# activator.net
KiCad netlist of a schematic drawn in Altium Designer
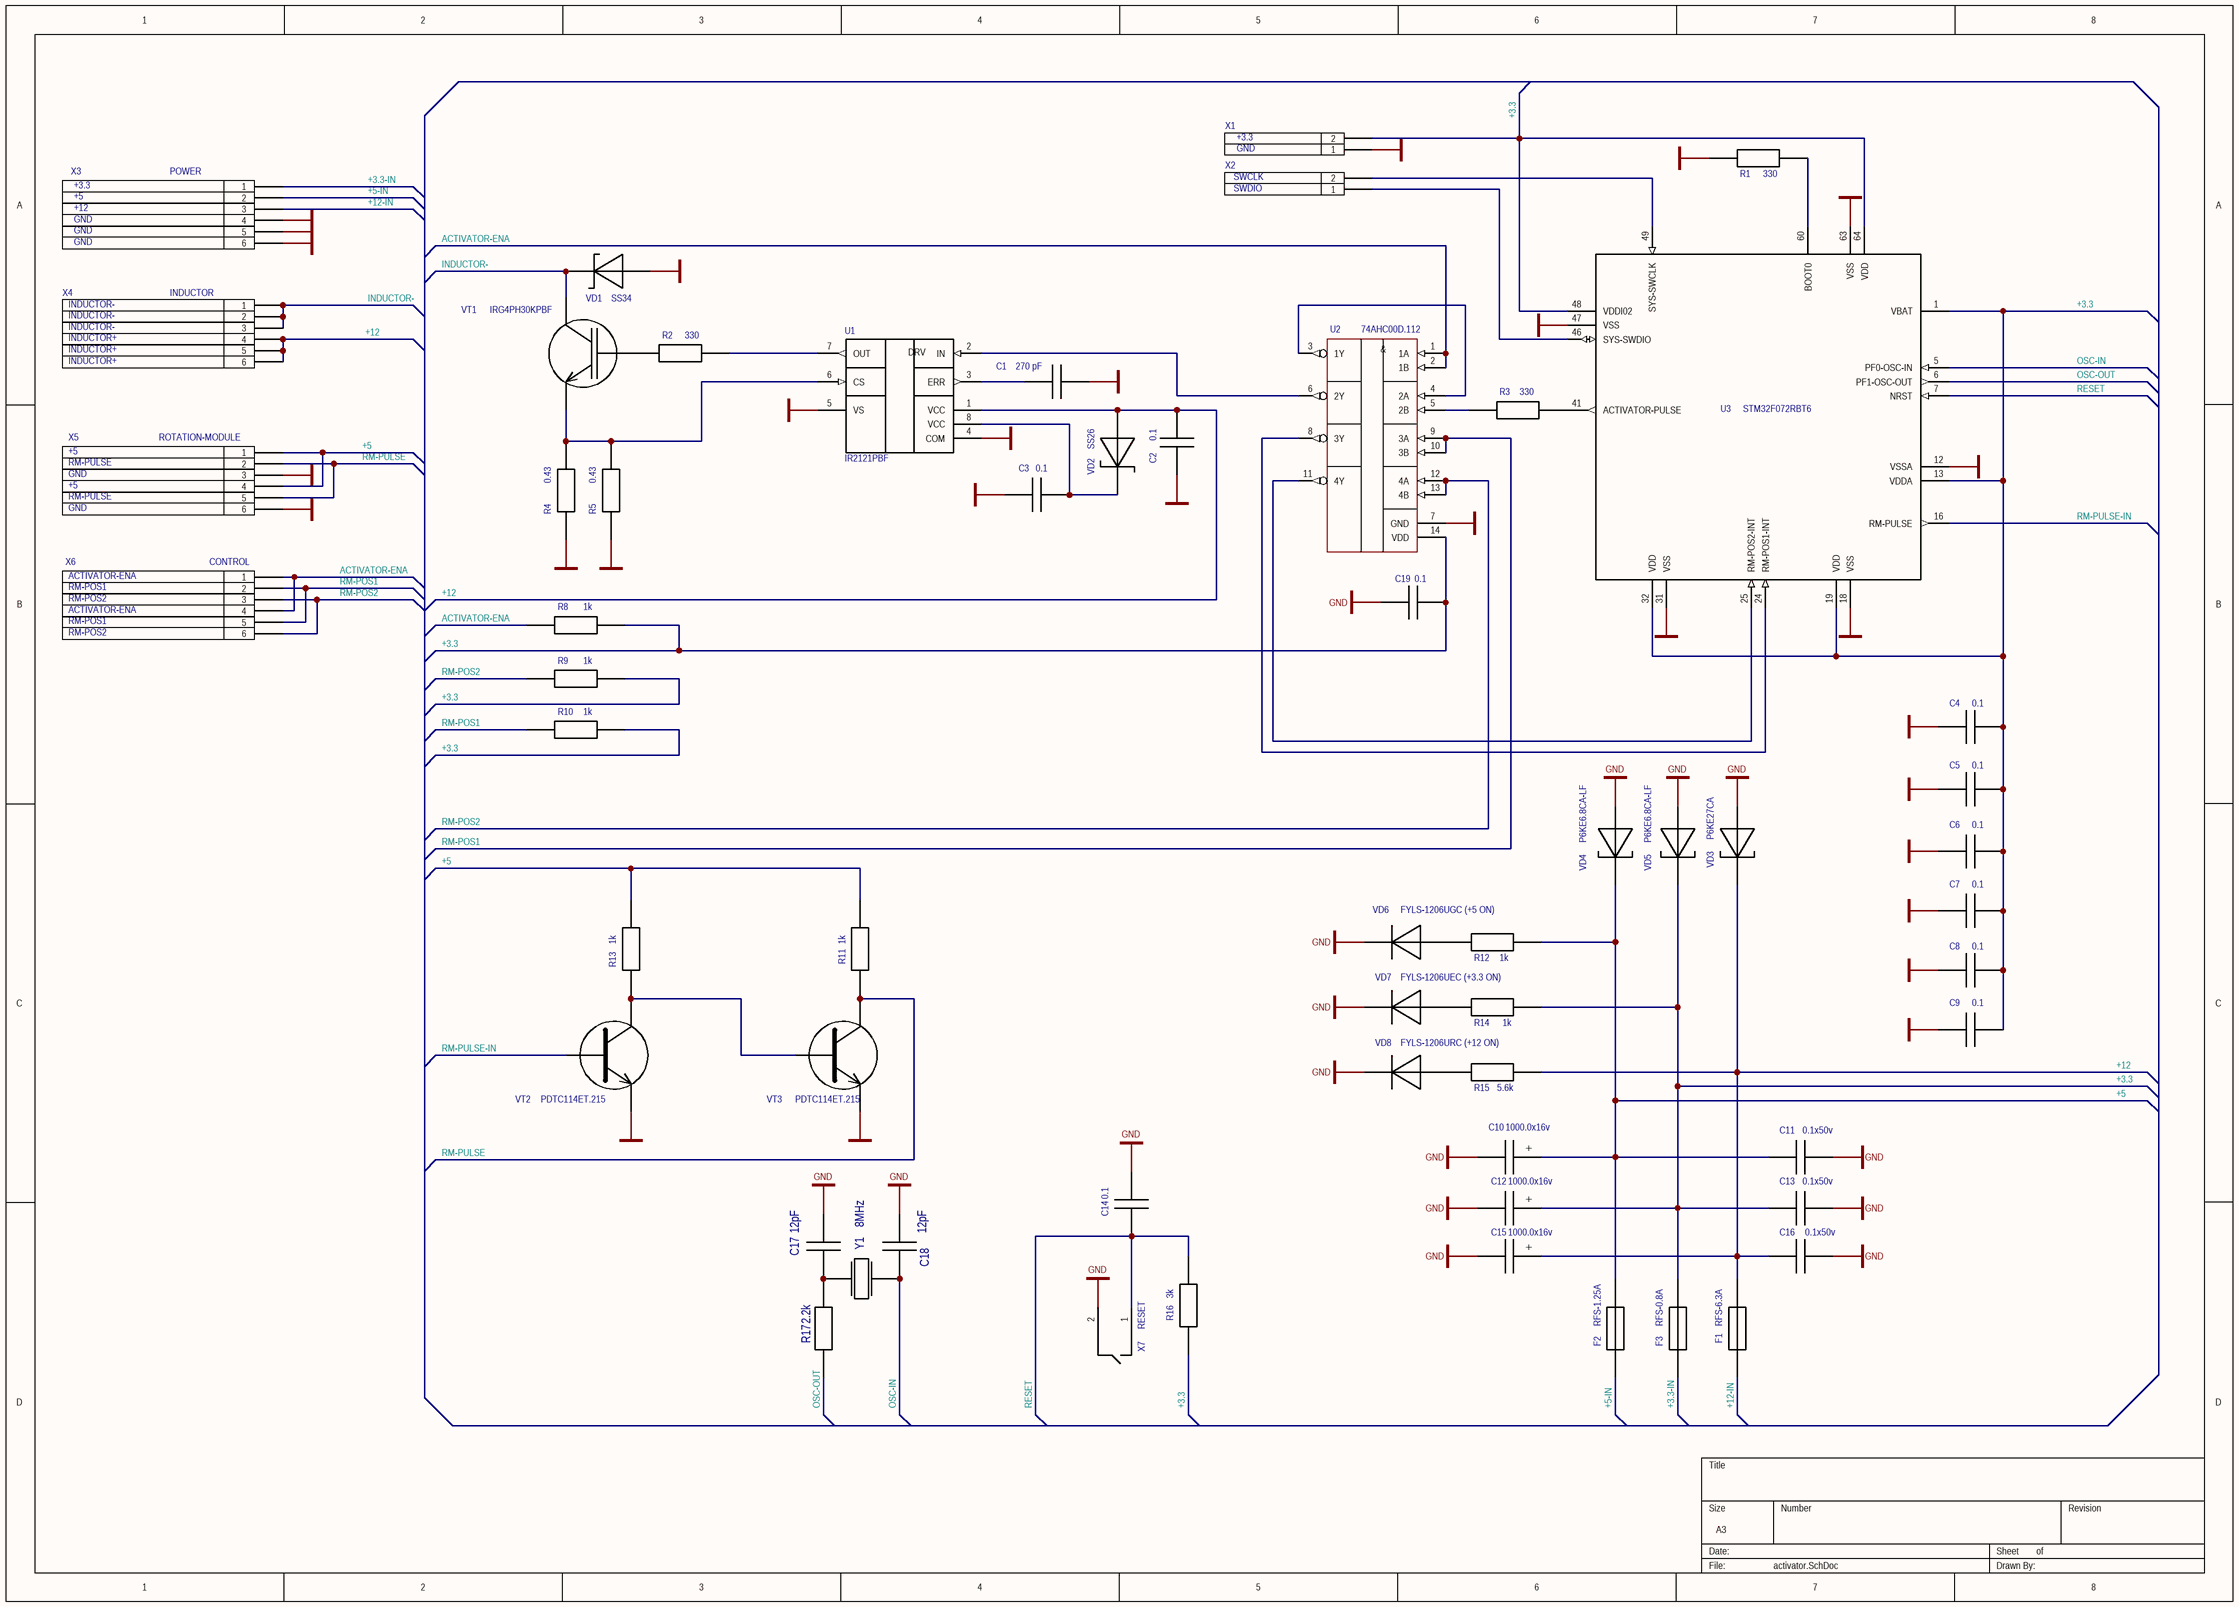
[diagram p0: activator.SchDoc]

(export (version "E")
  (design (tool "Eeschema 10.0.6"))
  (components
    (comp (ref "C1")
      (value "270 pF")
      (footprint "CAPC3216X05N")
      (description "SMD конденсатор")
      (libsource (lib "ulysses_library") (part "C"))
    )
    (comp (ref "C2")
      (value "0.1")
      (footprint "CAPC3216X05N")
      (description "SMD конденсатор")
      (libsource (lib "ulysses_library") (part "C"))
    )
    (comp (ref "C3")
      (value "0.1")
      (footprint "CAPC3216X05N")
      (description "SMD конденсатор")
      (libsource (lib "ulysses_library") (part "C"))
    )
    (comp (ref "C4")
      (value "0.1")
      (footprint "CAPC1608X05N")
      (description "SMD конденсатор")
      (libsource (lib "ulysses_library") (part "C"))
    )
    (comp (ref "C5")
      (value "0.1")
      (footprint "CAPC1608X05N")
      (description "SMD конденсатор")
      (libsource (lib "ulysses_library") (part "C"))
    )
    (comp (ref "C6")
      (value "0.1")
      (footprint "CAPC1608X05N")
      (description "SMD конденсатор")
      (libsource (lib "ulysses_library") (part "C"))
    )
    (comp (ref "C7")
      (value "0.1")
      (footprint "CAPC1608X05N")
      (description "SMD конденсатор")
      (libsource (lib "ulysses_library") (part "C"))
    )
    (comp (ref "C8")
      (value "0.1")
      (footprint "CAPC1608X05N")
      (description "SMD конденсатор")
      (libsource (lib "ulysses_library") (part "C"))
    )
    (comp (ref "C9")
      (value "0.1")
      (footprint "CAPC1608X05N")
      (description "SMD конденсатор")
      (libsource (lib "ulysses_library") (part "C"))
    )
    (comp (ref "C10")
      (value "1000.0x16v")
      (footprint "C-LOW-ESR-10-12.5")
      (description "Выводной электролит")
      (libsource (lib "ulysses_library") (part "C-LOW-ESR-RADIAL"))
    )
    (comp (ref "C11")
      (value "0.1x50v")
      (footprint "CAPC3216X05N")
      (description "SMD конденсатор")
      (libsource (lib "ulysses_library") (part "C"))
    )
    (comp (ref "C12")
      (value "1000.0x16v")
      (footprint "C-LOW-ESR-10-12.5")
      (description "Выводной электролит")
      (libsource (lib "ulysses_library") (part "C-LOW-ESR-RADIAL"))
    )
    (comp (ref "C13")
      (value "0.1x50v")
      (footprint "CAPC3216X05N")
      (description "SMD конденсатор")
      (libsource (lib "ulysses_library") (part "C"))
    )
    (comp (ref "C14")
      (value "0.1")
      (footprint "CAPC1608X05N")
      (description "SMD конденсатор")
      (libsource (lib "ulysses_library") (part "C"))
    )
    (comp (ref "C15")
      (value "1000.0x16v")
      (footprint "C-LOW-ESR-10-12.5")
      (description "Выводной электролит")
      (libsource (lib "ulysses_library") (part "C-LOW-ESR-RADIAL"))
    )
    (comp (ref "C16")
      (value "0.1x50v")
      (footprint "CAPC3216X05N")
      (description "SMD конденсатор")
      (libsource (lib "ulysses_library") (part "C"))
    )
    (comp (ref "C17")
      (value "12pF")
      (footprint "CAPC1608X05N")
      (description "SMD конденсатор")
      (libsource (lib "ulysses_library") (part "C"))
    )
    (comp (ref "C18")
      (value "12pF")
      (footprint "CAPC1608X05N")
      (description "SMD конденсатор")
      (libsource (lib "ulysses_library") (part "C"))
    )
    (comp (ref "C19")
      (value "0.1")
      (footprint "CAPC2012X04N")
      (description "SMD конденсатор")
      (libsource (lib "") (part "C_1"))
    )
    (comp (ref "F1")
      (value "RFS-6.3A")
      (footprint "MRT-FUSE")
      (description "Вставка плавкая")
      (libsource (lib "ulysses_library") (part "FUSE"))
    )
    (comp (ref "F2")
      (value "RFS-1.25A")
      (footprint "MRT-FUSE")
      (description "Вставка плавкая")
      (libsource (lib "ulysses_library") (part "FUSE"))
    )
    (comp (ref "F3")
      (value "RFS-0.8A")
      (footprint "MRT-FUSE")
      (description "Вставка плавкая")
      (libsource (lib "ulysses_library") (part "FUSE"))
    )
    (comp (ref "R1")
      (value "330")
      (footprint "RESC1608X05N")
      (description "SMD резистор")
      (libsource (lib "ulysses_library") (part "R"))
    )
    (comp (ref "R2")
      (value "330")
      (footprint "RESC3216X05N")
      (description "SMD резистор")
      (libsource (lib "ulysses_library") (part "R"))
    )
    (comp (ref "R3")
      (value "330")
      (footprint "RESC2012X04N")
      (description "SMD резистор")
      (libsource (lib "ulysses_library") (part "R"))
    )
    (comp (ref "R4")
      (value "0.43")
      (footprint "SQP-5W")
      (description "Резистор керамика 5 ватт")
      (libsource (lib "ulysses_library") (part "R5W"))
    )
    (comp (ref "R5")
      (value "0.43")
      (footprint "SQP-5W")
      (description "Резистор керамика 5 ватт")
      (libsource (lib "ulysses_library") (part "R5W"))
    )
    (comp (ref "R8")
      (value "1k")
      (footprint "RESC3216X05N")
      (description "SMD резистор")
      (libsource (lib "ulysses_library") (part "R"))
    )
    (comp (ref "R9")
      (value "1k")
      (footprint "RESC3216X05N")
      (description "SMD резистор")
      (libsource (lib "ulysses_library") (part "R"))
    )
    (comp (ref "R10")
      (value "1k")
      (footprint "RESC3216X05N")
      (description "SMD резистор")
      (libsource (lib "ulysses_library") (part "R"))
    )
    (comp (ref "R11")
      (value "1k")
      (footprint "RESC2012X04N")
      (description "SMD резистор")
      (libsource (lib "ulysses_library") (part "R"))
    )
    (comp (ref "R12")
      (value "1k")
      (footprint "RESC2012X04N")
      (description "SMD резистор")
      (libsource (lib "ulysses_library") (part "R"))
    )
    (comp (ref "R13")
      (value "1k")
      (footprint "RESC2012X04N")
      (description "SMD резистор")
      (libsource (lib "ulysses_library") (part "R"))
    )
    (comp (ref "R14")
      (value "1k")
      (footprint "RESC2012X04N")
      (description "SMD резистор")
      (libsource (lib "ulysses_library") (part "R"))
    )
    (comp (ref "R15")
      (value "5.6k")
      (footprint "RESC2012X04N")
      (description "SMD резистор")
      (libsource (lib "ulysses_library") (part "R"))
    )
    (comp (ref "R16")
      (value "3k")
      (footprint "RESC1608X05N")
      (description "SMD резистор")
      (libsource (lib "ulysses_library") (part "R"))
    )
    (comp (ref "R17")
      (value "2.2k")
      (footprint "RESC1608X05N")
      (description "SMD резистор")
      (libsource (lib "ulysses_library") (part "R"))
    )
    (comp (ref "U1")
      (value "IR2121PBF")
      (footprint "DIP8")
      (description "IGBT-MOSFET DRIVER")
      (libsource (lib "ulysses_library") (part "IR2121PBF"))
    )
    (comp (ref "U2")
      (value "74AHC00D.112")
      (footprint "SOIC127P600X175-14N")
      (description "2И-НЕ 4 ВЕНТИЛЯ")
      (libsource (lib "ulysses_library") (part "74AHC00D.112"))
    )
    (comp (ref "U3")
      (value "STM32F072RBT6")
      (footprint "TSQFP50P1200X1200X160-64N")
      (description "Микроконтроллер")
      (libsource (lib "ulysses_library") (part "STM32F072RBT6"))
    )
    (comp (ref "VD1")
      (value "SS34")
      (footprint "DIOM6959X26N")
      (description "Диод Шоттки")
      (libsource (lib "ulysses_library") (part "SS34"))
    )
    (comp (ref "VD2")
      (value "SS26")
      (footprint "DIOM4336X21N")
      (description "диод Шоттки")
      (libsource (lib "ulysses_library") (part "SS26"))
    )
    (comp (ref "VD3")
      (value "P6KE27CA")
      (footprint "P6KE27CA")
      (description "Cупрессор")
      (libsource (lib "ulysses_library") (part "P6KE27CA"))
    )
    (comp (ref "VD4")
      (value "P6KE6.8CA-LF")
      (footprint "P6KE27CA")
      (description "Cупрессор")
      (libsource (lib "ulysses_library") (part "P6KE27CA"))
    )
    (comp (ref "VD5")
      (value "P6KE6.8CA-LF")
      (footprint "P6KE27CA")
      (description "Cупрессор")
      (libsource (lib "ulysses_library") (part "P6KE27CA"))
    )
    (comp (ref "VD6")
      (value "FYLS-1206UGC (+5 ON)")
      (footprint "CAPMP3216X11N")
      (description "Светодиод")
      (libsource (lib "ulysses_library") (part "FYLS-1206"))
    )
    (comp (ref "VD7")
      (value "FYLS-1206UEC (+3.3 ON)")
      (footprint "CAPMP3216X11N")
      (description "Светодиод")
      (libsource (lib "ulysses_library") (part "FYLS-1206"))
    )
    (comp (ref "VD8")
      (value "FYLS-1206URC (+12 ON)")
      (footprint "CAPMP3216X11N")
      (description "Светодиод")
      (libsource (lib "ulysses_library") (part "FYLS-1206"))
    )
    (comp (ref "VT1")
      (value "IRG4PH30KPBF")
      (footprint "TO-247AC")
      (description "IGBT transistor")
      (libsource (lib "ulysses_library") (part "IRG4PH30KPBF"))
    )
    (comp (ref "VT2")
      (value "PDTC114ET.215")
      (footprint "SOT95P238X102-3N")
      (description "NPN transistor with bias circuit")
      (libsource (lib "ulysses_library") (part "PDTC114ET.215"))
    )
    (comp (ref "VT3")
      (value "PDTC114ET.215")
      (footprint "SOT95P238X102-3N")
      (description "NPN transistor with bias circuit")
      (libsource (lib "ulysses_library") (part "PDTC114ET.215"))
    )
    (comp (ref "X1")
      (value "Jamper ZL201")
      (footprint "ZL201-2")
      (libsource (lib "") (part "Jamper ZL201_1"))
    )
    (comp (ref "X2")
      (value "Jamper ZL201")
      (footprint "ZL201-2")
      (libsource (lib "ulysses_library") (part "Jamper ZL201"))
    )
    (comp (ref "X3")
      (value "POWER")
      (footprint "MINI-FIT-6WAY-SM")
      (libsource (lib "") (part "MINI-FIT-6-WAY-M_1"))
    )
    (comp (ref "X4")
      (value "INDUCTOR")
      (footprint "MINI-FIT-6WAY-SM")
      (libsource (lib "ulysses_library") (part "MINI-FIT-6-WAY-M"))
    )
    (comp (ref "X5")
      (value "ROTATION-MODULE")
      (footprint "MINI-FIT-6WAY-SM")
      (libsource (lib "ulysses_library") (part "MINI-FIT-6-WAY-M"))
    )
    (comp (ref "X6")
      (value "CONTROL")
      (footprint "MINI-FIT-6WAY-SM")
      (libsource (lib "ulysses_library") (part "MINI-FIT-6-WAY-M"))
    )
    (comp (ref "X7")
      (value "RESET")
      (footprint "TACT SWITCH")
      (libsource (lib "ulysses_library") (part "TACT SWITCH"))
    )
    (comp (ref "Y1")
      (value "8MHz")
      (footprint "ulysses_library:HC49LT")
      (description "Кварцевый резонатор")
      (libsource (lib "ulysses_library") (part "CERAMIC-RESONATOR"))
    )
  )
  (nets
    (net (code "1") (name "/+3.3") (class "Default")
      (node (ref "C12") (pin "1") (pinfunction "+_1") (pintype "passive"))
      (node (ref "C13") (pin "1") (pinfunction "1_1") (pintype "passive"))
      (node (ref "C19") (pin "2") (pinfunction "2_2") (pintype "passive"))
      (node (ref "C4") (pin "2") (pinfunction "2_2") (pintype "passive"))
      (node (ref "C5") (pin "2") (pinfunction "2_2") (pintype "passive"))
      (node (ref "C6") (pin "2") (pinfunction "2_2") (pintype "passive"))
      (node (ref "C7") (pin "2") (pinfunction "2_2") (pintype "passive"))
      (node (ref "C8") (pin "2") (pinfunction "2_2") (pintype "passive"))
      (node (ref "C9") (pin "2") (pinfunction "2_2") (pintype "passive"))
      (node (ref "F3") (pin "1") (pinfunction "1_1") (pintype "passive"))
      (node (ref "R10") (pin "2") (pinfunction "2_2") (pintype "passive"))
      (node (ref "R14") (pin "2") (pinfunction "2_2") (pintype "passive"))
      (node (ref "R16") (pin "1") (pintype "passive"))
      (node (ref "R8") (pin "2") (pinfunction "2_2") (pintype "passive"))
      (node (ref "R9") (pin "2") (pinfunction "2_2") (pintype "passive"))
      (node (ref "U2") (pin "14") (pinfunction "VDD_14") (pintype "power_in"))
      (node (ref "U3") (pin "1") (pinfunction "VBAT_1") (pintype "passive"))
      (node (ref "U3") (pin "13") (pinfunction "VDDA_13") (pintype "passive"))
      (node (ref "U3") (pin "19") (pinfunction "VDD_19") (pintype "passive"))
      (node (ref "U3") (pin "32") (pinfunction "VDD_32") (pintype "passive"))
      (node (ref "U3") (pin "48") (pinfunction "VDDI02_48") (pintype "passive"))
      (node (ref "U3") (pin "64") (pinfunction "VDD_64") (pintype "passive"))
      (node (ref "VD5") (pin "K") (pinfunction "K_K") (pintype "passive"))
      (node (ref "X1") (pin "2") (pinfunction "2_2") (pintype "passive"))
    )
    (net (code "2") (name "/+3.3-IN") (class "Default")
      (node (ref "F3") (pin "2") (pinfunction "2_2") (pintype "passive"))
      (node (ref "X3") (pin "1") (pinfunction "1_1") (pintype "passive"))
    )
    (net (code "3") (name "/+5") (class "Default")
      (node (ref "C10") (pin "1") (pinfunction "+_1") (pintype "passive"))
      (node (ref "C11") (pin "1") (pinfunction "1_1") (pintype "passive"))
      (node (ref "F2") (pin "1") (pinfunction "1_1") (pintype "passive"))
      (node (ref "R11") (pin "2") (pinfunction "2_2") (pintype "passive"))
      (node (ref "R12") (pin "2") (pinfunction "2_2") (pintype "passive"))
      (node (ref "R13") (pin "2") (pinfunction "2_2") (pintype "passive"))
      (node (ref "VD4") (pin "K") (pinfunction "K_K") (pintype "passive"))
      (node (ref "X5") (pin "1") (pinfunction "1_1") (pintype "passive"))
      (node (ref "X5") (pin "4") (pinfunction "4_4") (pintype "passive"))
    )
    (net (code "4") (name "/+5-IN") (class "Default")
      (node (ref "F2") (pin "2") (pinfunction "2_2") (pintype "passive"))
      (node (ref "X3") (pin "2") (pinfunction "2_2") (pintype "passive"))
    )
    (net (code "5") (name "/+12") (class "Default")
      (node (ref "C15") (pin "1") (pinfunction "+_1") (pintype "passive"))
      (node (ref "C16") (pin "1") (pinfunction "1_1") (pintype "passive"))
      (node (ref "C2") (pin "2") (pinfunction "2_2") (pintype "passive"))
      (node (ref "F1") (pin "1") (pinfunction "1_1") (pintype "passive"))
      (node (ref "R15") (pin "2") (pinfunction "2_2") (pintype "passive"))
      (node (ref "U1") (pin "1") (pinfunction "VCC_1") (pintype "power_in"))
      (node (ref "VD2") (pin "2") (pinfunction "A_2") (pintype "passive"))
      (node (ref "VD3") (pin "K") (pinfunction "K_K") (pintype "passive"))
      (node (ref "X4") (pin "4") (pinfunction "4_4") (pintype "passive"))
      (node (ref "X4") (pin "5") (pinfunction "5_5") (pintype "passive"))
      (node (ref "X4") (pin "6") (pinfunction "6_6") (pintype "passive"))
    )
    (net (code "6") (name "/+12-IN") (class "Default")
      (node (ref "F1") (pin "2") (pinfunction "2_2") (pintype "passive"))
      (node (ref "X3") (pin "3") (pinfunction "3_3") (pintype "passive"))
    )
    (net (code "7") (name "/ACTIVATOR-ENA") (class "Default")
      (node (ref "R8") (pin "1") (pintype "passive"))
      (node (ref "U2") (pin "1") (pinfunction "1A_1") (pintype "input"))
      (node (ref "U2") (pin "2") (pinfunction "1B_2") (pintype "input"))
      (node (ref "X6") (pin "1") (pinfunction "1_1") (pintype "passive"))
      (node (ref "X6") (pin "4") (pinfunction "4_4") (pintype "passive"))
    )
    (net (code "8") (name "/INDUCTOR-") (class "Default")
      (node (ref "VD1") (pin "1") (pinfunction "C_1") (pintype "passive"))
      (node (ref "VT1") (pin "2") (pinfunction "C_2") (pintype "power_in"))
      (node (ref "X4") (pin "1") (pinfunction "1_1") (pintype "passive"))
      (node (ref "X4") (pin "2") (pinfunction "2_2") (pintype "passive"))
      (node (ref "X4") (pin "3") (pinfunction "3_3") (pintype "passive"))
    )
    (net (code "9") (name "/OSC-IN") (class "Default")
      (node (ref "C18") (pin "2") (pinfunction "2_2") (pintype "passive"))
      (node (ref "U3") (pin "5") (pinfunction "PF0-OSC-IN_5") (pintype "input"))
      (node (ref "Y1") (pin "2") (pinfunction "2_2") (pintype "passive"))
    )
    (net (code "10") (name "/OSC-OUT") (class "Default")
      (node (ref "R17") (pin "2") (pinfunction "2_2") (pintype "passive"))
      (node (ref "U3") (pin "6") (pinfunction "PF1-OSC-OUT_6") (pintype "output"))
    )
    (net (code "11") (name "/RESET") (class "Default")
      (node (ref "C14") (pin "1") (pinfunction "1_1") (pintype "passive"))
      (node (ref "R16") (pin "2") (pinfunction "2_2") (pintype "passive"))
      (node (ref "U3") (pin "7") (pinfunction "NRST_7") (pintype "input"))
      (node (ref "X7") (pin "1") (pinfunction "1_1") (pintype "passive"))
    )
    (net (code "12") (name "/RM-POS1") (class "Default")
      (node (ref "R10") (pin "1") (pintype "passive"))
      (node (ref "U2") (pin "10") (pinfunction "3B_10") (pintype "input"))
      (node (ref "U2") (pin "9") (pinfunction "3A_9") (pintype "input"))
      (node (ref "X6") (pin "2") (pinfunction "2_2") (pintype "passive"))
      (node (ref "X6") (pin "5") (pinfunction "5_5") (pintype "passive"))
    )
    (net (code "13") (name "/RM-POS2") (class "Default")
      (node (ref "R9") (pin "1") (pintype "passive"))
      (node (ref "U2") (pin "12") (pinfunction "4A_12") (pintype "input"))
      (node (ref "U2") (pin "13") (pinfunction "4B_13") (pintype "input"))
      (node (ref "X6") (pin "3") (pinfunction "3_3") (pintype "passive"))
      (node (ref "X6") (pin "6") (pinfunction "6_6") (pintype "passive"))
    )
    (net (code "14") (name "/RM-PULSE") (class "Default")
      (node (ref "R11") (pin "1") (pintype "passive"))
      (node (ref "VT3") (pin "3") (pinfunction "C_3") (pintype "power_in"))
      (node (ref "X5") (pin "2") (pinfunction "2_2") (pintype "passive"))
      (node (ref "X5") (pin "5") (pinfunction "5_5") (pintype "passive"))
    )
    (net (code "15") (name "/RM-PULSE-IN") (class "Default")
      (node (ref "U3") (pin "16") (pinfunction "RM-PULSE_16") (pintype "output"))
      (node (ref "VT2") (pin "1") (pinfunction "B_1") (pintype "power_in"))
    )
    (net (code "16") (name "GND") (class "Default")
      (node (ref "C1") (pin "2") (pinfunction "2_2") (pintype "passive"))
      (node (ref "C10") (pin "2") (pinfunction "2_2") (pintype "passive"))
      (node (ref "C11") (pin "2") (pinfunction "2_2") (pintype "passive"))
      (node (ref "C12") (pin "2") (pinfunction "2_2") (pintype "passive"))
      (node (ref "C13") (pin "2") (pinfunction "2_2") (pintype "passive"))
      (node (ref "C14") (pin "2") (pinfunction "2_2") (pintype "passive"))
      (node (ref "C15") (pin "2") (pinfunction "2_2") (pintype "passive"))
      (node (ref "C16") (pin "2") (pinfunction "2_2") (pintype "passive"))
      (node (ref "C17") (pin "1") (pinfunction "1_1") (pintype "passive"))
      (node (ref "C18") (pin "1") (pinfunction "1_1") (pintype "passive"))
      (node (ref "C19") (pin "1") (pinfunction "1_1") (pintype "passive"))
      (node (ref "C2") (pin "1") (pinfunction "1_1") (pintype "passive"))
      (node (ref "C3") (pin "1") (pinfunction "1_1") (pintype "passive"))
      (node (ref "C4") (pin "1") (pinfunction "1_1") (pintype "passive"))
      (node (ref "C5") (pin "1") (pinfunction "1_1") (pintype "passive"))
      (node (ref "C6") (pin "1") (pinfunction "1_1") (pintype "passive"))
      (node (ref "C7") (pin "1") (pinfunction "1_1") (pintype "passive"))
      (node (ref "C8") (pin "1") (pinfunction "1_1") (pintype "passive"))
      (node (ref "C9") (pin "1") (pinfunction "1_1") (pintype "passive"))
      (node (ref "R1") (pin "1") (pintype "passive"))
      (node (ref "R4") (pin "1") (pinfunction "1_1") (pintype "passive"))
      (node (ref "R5") (pin "1") (pinfunction "1_1") (pintype "passive"))
      (node (ref "U1") (pin "4") (pinfunction "COM_4") (pintype "power_in"))
      (node (ref "U1") (pin "5") (pinfunction "VS_5") (pintype "power_in"))
      (node (ref "U2") (pin "7") (pinfunction "GND_7") (pintype "power_in"))
      (node (ref "U3") (pin "12") (pinfunction "VSSA_12") (pintype "passive"))
      (node (ref "U3") (pin "18") (pinfunction "VSS_18") (pintype "passive"))
      (node (ref "U3") (pin "31") (pinfunction "VSS_31") (pintype "passive"))
      (node (ref "U3") (pin "47") (pinfunction "VSS_47") (pintype "passive"))
      (node (ref "U3") (pin "63") (pinfunction "VSS_63") (pintype "passive"))
      (node (ref "VD1") (pin "2") (pinfunction "A_2") (pintype "passive"))
      (node (ref "VD3") (pin "A") (pinfunction "A_A") (pintype "passive"))
      (node (ref "VD4") (pin "A") (pinfunction "A_A") (pintype "passive"))
      (node (ref "VD5") (pin "A") (pinfunction "A_A") (pintype "passive"))
      (node (ref "VD6") (pin "1") (pinfunction "C_1") (pintype "power_in"))
      (node (ref "VD7") (pin "1") (pinfunction "C_1") (pintype "power_in"))
      (node (ref "VD8") (pin "1") (pinfunction "C_1") (pintype "power_in"))
      (node (ref "VT2") (pin "2") (pinfunction "E_2") (pintype "power_in"))
      (node (ref "VT3") (pin "2") (pinfunction "E_2") (pintype "power_in"))
      (node (ref "X1") (pin "1") (pinfunction "1_1") (pintype "passive"))
      (node (ref "X3") (pin "4") (pinfunction "4_4") (pintype "passive"))
      (node (ref "X3") (pin "5") (pinfunction "5_5") (pintype "passive"))
      (node (ref "X3") (pin "6") (pinfunction "6_6") (pintype "passive"))
      (node (ref "X5") (pin "3") (pinfunction "3_3") (pintype "passive"))
      (node (ref "X5") (pin "6") (pinfunction "6_6") (pintype "passive"))
      (node (ref "X7") (pin "2") (pinfunction "2_2") (pintype "passive"))
    )
    (net (code "17") (name "Net-(C17-Pad2)") (class "Default")
      (node (ref "C17") (pin "2") (pinfunction "2_2") (pintype "passive"))
      (node (ref "R17") (pin "1") (pintype "passive"))
      (node (ref "Y1") (pin "1") (pinfunction "1_1") (pintype "passive"))
    )
    (net (code "18") (name "Net-(U1-CS)") (class "Default")
      (node (ref "R4") (pin "2") (pinfunction "2_2") (pintype "passive"))
      (node (ref "R5") (pin "2") (pinfunction "2_2") (pintype "passive"))
      (node (ref "U1") (pin "6") (pinfunction "CS_6") (pintype "input"))
      (node (ref "VT1") (pin "3") (pinfunction "E_3") (pintype "power_in"))
    )
    (net (code "19") (name "Net-(U1-ERR)") (class "Default")
      (node (ref "C1") (pin "1") (pinfunction "1_1") (pintype "passive"))
      (node (ref "U1") (pin "3") (pinfunction "ERR_3") (pintype "output"))
    )
    (net (code "20") (name "Net-(U1-IN)") (class "Default")
      (node (ref "U1") (pin "2") (pinfunction "IN_2") (pintype "input"))
      (node (ref "U2") (pin "6") (pinfunction "2Y_6") (pintype "output"))
    )
    (net (code "21") (name "Net-(U1-OUT)") (class "Default")
      (node (ref "R2") (pin "2") (pinfunction "2_2") (pintype "passive"))
      (node (ref "U1") (pin "7") (pinfunction "OUT_7") (pintype "output"))
    )
    (net (code "22") (name "Net-(U2-1Y)") (class "Default")
      (node (ref "U2") (pin "3") (pinfunction "1Y_3") (pintype "output"))
      (node (ref "U2") (pin "4") (pinfunction "2A_4") (pintype "input"))
    )
    (net (code "23") (name "Net-(U2-2B)") (class "Default")
      (node (ref "R3") (pin "1") (pintype "passive"))
      (node (ref "U2") (pin "5") (pinfunction "2B_5") (pintype "input"))
    )
    (net (code "24") (name "Net-(U2-3Y)") (class "Default")
      (node (ref "U2") (pin "8") (pinfunction "3Y_8") (pintype "output"))
      (node (ref "U3") (pin "24") (pinfunction "RM-POS1-INT_24") (pintype "input"))
    )
    (net (code "25") (name "Net-(U2-4Y)") (class "Default")
      (node (ref "U2") (pin "11") (pinfunction "4Y_11") (pintype "output"))
      (node (ref "U3") (pin "25") (pinfunction "RM-POS2-INT_25") (pintype "input"))
    )
    (net (code "26") (name "Net-(U3-ACTIVATOR-PULSE)") (class "Default")
      (node (ref "R3") (pin "2") (pinfunction "2_2") (pintype "passive"))
      (node (ref "U3") (pin "41") (pinfunction "ACTIVATOR-PULSE_41") (pintype "output"))
    )
    (net (code "27") (name "Net-(U3-BOOT0)") (class "Default")
      (node (ref "R1") (pin "2") (pinfunction "2_2") (pintype "passive"))
      (node (ref "U3") (pin "60") (pinfunction "BOOT0_60") (pintype "passive"))
    )
    (net (code "28") (name "Net-(U3-SYS-SWCLK)") (class "Default")
      (node (ref "U3") (pin "49") (pinfunction "SYS-SWCLK_49") (pintype "input"))
      (node (ref "X2") (pin "2") (pinfunction "2_2") (pintype "passive"))
    )
    (net (code "29") (name "Net-(U3-SYS-SWDIO)") (class "Default")
      (node (ref "U3") (pin "46") (pinfunction "SYS-SWDIO_46") (pintype "bidirectional"))
      (node (ref "X2") (pin "1") (pinfunction "1_1") (pintype "passive"))
    )
    (net (code "30") (name "Net-(VD2-C)") (class "Default")
      (node (ref "C3") (pin "2") (pinfunction "2_2") (pintype "passive"))
      (node (ref "U1") (pin "8") (pinfunction "VCC_8") (pintype "power_in"))
      (node (ref "VD2") (pin "1") (pinfunction "C_1") (pintype "passive"))
    )
    (net (code "31") (name "Net-(VD6-A)") (class "Default")
      (node (ref "R12") (pin "1") (pintype "passive"))
      (node (ref "VD6") (pin "2") (pinfunction "A_2") (pintype "power_in"))
    )
    (net (code "32") (name "Net-(VD7-A)") (class "Default")
      (node (ref "R14") (pin "1") (pintype "passive"))
      (node (ref "VD7") (pin "2") (pinfunction "A_2") (pintype "power_in"))
    )
    (net (code "33") (name "Net-(VD8-A)") (class "Default")
      (node (ref "R15") (pin "1") (pintype "passive"))
      (node (ref "VD8") (pin "2") (pinfunction "A_2") (pintype "power_in"))
    )
    (net (code "34") (name "Net-(VT1-G)") (class "Default")
      (node (ref "R2") (pin "1") (pintype "passive"))
      (node (ref "VT1") (pin "1") (pinfunction "G_1") (pintype "power_in"))
    )
    (net (code "35") (name "Net-(VT2-C)") (class "Default")
      (node (ref "R13") (pin "1") (pintype "passive"))
      (node (ref "VT2") (pin "3") (pinfunction "C_3") (pintype "power_in"))
      (node (ref "VT3") (pin "1") (pinfunction "B_1") (pintype "power_in"))
    )
    (net (code "36") (name "unconnected-(U3-PA0-Pad14)") (class "Default")
      (node (ref "U3") (pin "14") (pinfunction "PA0_14") (pintype "passive"))
    )
    (net (code "37") (name "unconnected-(U3-PA1-Pad15)") (class "Default")
      (node (ref "U3") (pin "15") (pinfunction "PA1_15") (pintype "passive"))
    )
    (net (code "38") (name "unconnected-(U3-PA3-Pad17)") (class "Default")
      (node (ref "U3") (pin "17") (pinfunction "PA3_17") (pintype "passive"))
    )
    (net (code "39") (name "unconnected-(U3-PA4-Pad20)") (class "Default")
      (node (ref "U3") (pin "20") (pinfunction "PA4_20") (pintype "passive"))
    )
    (net (code "40") (name "unconnected-(U3-PA5-Pad21)") (class "Default")
      (node (ref "U3") (pin "21") (pinfunction "PA5_21") (pintype "passive"))
    )
    (net (code "41") (name "unconnected-(U3-PA6-Pad22)") (class "Default")
      (node (ref "U3") (pin "22") (pinfunction "PA6_22") (pintype "passive"))
    )
    (net (code "42") (name "unconnected-(U3-PA7-Pad23)") (class "Default")
      (node (ref "U3") (pin "23") (pinfunction "PA7_23") (pintype "passive"))
    )
    (net (code "43") (name "unconnected-(U3-PA9-Pad42)") (class "Default")
      (node (ref "U3") (pin "42") (pinfunction "PA9_42") (pintype "passive"))
    )
    (net (code "44") (name "unconnected-(U3-PA10-Pad43)") (class "Default")
      (node (ref "U3") (pin "43") (pinfunction "PA10_43") (pintype "passive"))
    )
    (net (code "45") (name "unconnected-(U3-PA11-Pad44)") (class "Default")
      (node (ref "U3") (pin "44") (pinfunction "PA11_44") (pintype "passive"))
    )
    (net (code "46") (name "unconnected-(U3-PA12-Pad45)") (class "Default")
      (node (ref "U3") (pin "45") (pinfunction "PA12_45") (pintype "passive"))
    )
    (net (code "47") (name "unconnected-(U3-PA15-Pad50)") (class "Default")
      (node (ref "U3") (pin "50") (pinfunction "PA15_50") (pintype "passive"))
    )
    (net (code "48") (name "unconnected-(U3-PB0-Pad26)") (class "Default")
      (node (ref "U3") (pin "26") (pinfunction "PB0_26") (pintype "passive"))
    )
    (net (code "49") (name "unconnected-(U3-PB1-Pad27)") (class "Default")
      (node (ref "U3") (pin "27") (pinfunction "PB1_27") (pintype "passive"))
    )
    (net (code "50") (name "unconnected-(U3-PB2-Pad28)") (class "Default")
      (node (ref "U3") (pin "28") (pinfunction "PB2_28") (pintype "passive"))
    )
    (net (code "51") (name "unconnected-(U3-PB3-Pad55)") (class "Default")
      (node (ref "U3") (pin "55") (pinfunction "PB3_55") (pintype "passive"))
    )
    (net (code "52") (name "unconnected-(U3-PB4-Pad56)") (class "Default")
      (node (ref "U3") (pin "56") (pinfunction "PB4_56") (pintype "passive"))
    )
    (net (code "53") (name "unconnected-(U3-PB5-Pad57)") (class "Default")
      (node (ref "U3") (pin "57") (pinfunction "PB5_57") (pintype "passive"))
    )
    (net (code "54") (name "unconnected-(U3-PB6-Pad58)") (class "Default")
      (node (ref "U3") (pin "58") (pinfunction "PB6_58") (pintype "passive"))
    )
    (net (code "55") (name "unconnected-(U3-PB7-Pad59)") (class "Default")
      (node (ref "U3") (pin "59") (pinfunction "PB7_59") (pintype "passive"))
    )
    (net (code "56") (name "unconnected-(U3-PB8-Pad61)") (class "Default")
      (node (ref "U3") (pin "61") (pinfunction "PB8_61") (pintype "passive"))
    )
    (net (code "57") (name "unconnected-(U3-PB9-Pad62)") (class "Default")
      (node (ref "U3") (pin "62") (pinfunction "PB9_62") (pintype "passive"))
    )
    (net (code "58") (name "unconnected-(U3-PB10-Pad29)") (class "Default")
      (node (ref "U3") (pin "29") (pinfunction "PB10_29") (pintype "passive"))
    )
    (net (code "59") (name "unconnected-(U3-PB11-Pad30)") (class "Default")
      (node (ref "U3") (pin "30") (pinfunction "PB11_30") (pintype "passive"))
    )
    (net (code "60") (name "unconnected-(U3-PB12-Pad33)") (class "Default")
      (node (ref "U3") (pin "33") (pinfunction "PB12_33") (pintype "passive"))
    )
    (net (code "61") (name "unconnected-(U3-PB13-Pad34)") (class "Default")
      (node (ref "U3") (pin "34") (pinfunction "PB13_34") (pintype "passive"))
    )
    (net (code "62") (name "unconnected-(U3-PB14-Pad35)") (class "Default")
      (node (ref "U3") (pin "35") (pinfunction "PB14_35") (pintype "passive"))
    )
    (net (code "63") (name "unconnected-(U3-PB15-Pad36)") (class "Default")
      (node (ref "U3") (pin "36") (pinfunction "PB15_36") (pintype "passive"))
    )
    (net (code "64") (name "unconnected-(U3-PC0-Pad8)") (class "Default")
      (node (ref "U3") (pin "8") (pinfunction "PC0_8") (pintype "passive"))
    )
    (net (code "65") (name "unconnected-(U3-PC1-Pad9)") (class "Default")
      (node (ref "U3") (pin "9") (pinfunction "PC1_9") (pintype "passive"))
    )
    (net (code "66") (name "unconnected-(U3-PC2-Pad10)") (class "Default")
      (node (ref "U3") (pin "10") (pinfunction "PC2_10") (pintype "passive"))
    )
    (net (code "67") (name "unconnected-(U3-PC3-Pad11)") (class "Default")
      (node (ref "U3") (pin "11") (pinfunction "PC3_11") (pintype "passive"))
    )
    (net (code "68") (name "unconnected-(U3-PC6-Pad37)") (class "Default")
      (node (ref "U3") (pin "37") (pinfunction "PC6_37") (pintype "passive"))
    )
    (net (code "69") (name "unconnected-(U3-PC7-Pad38)") (class "Default")
      (node (ref "U3") (pin "38") (pinfunction "PC7_38") (pintype "passive"))
    )
    (net (code "70") (name "unconnected-(U3-PC8-Pad39)") (class "Default")
      (node (ref "U3") (pin "39") (pinfunction "PC8_39") (pintype "passive"))
    )
    (net (code "71") (name "unconnected-(U3-PC9-Pad40)") (class "Default")
      (node (ref "U3") (pin "40") (pinfunction "PC9_40") (pintype "passive"))
    )
    (net (code "72") (name "unconnected-(U3-PC10-Pad51)") (class "Default")
      (node (ref "U3") (pin "51") (pinfunction "PC10_51") (pintype "passive"))
    )
    (net (code "73") (name "unconnected-(U3-PC11-Pad52)") (class "Default")
      (node (ref "U3") (pin "52") (pinfunction "PC11_52") (pintype "passive"))
    )
    (net (code "74") (name "unconnected-(U3-PC12-Pad53)") (class "Default")
      (node (ref "U3") (pin "53") (pinfunction "PC12_53") (pintype "passive"))
    )
    (net (code "75") (name "unconnected-(U3-PC13-Pad2)") (class "Default")
      (node (ref "U3") (pin "2") (pinfunction "PC13_2") (pintype "passive"))
    )
    (net (code "76") (name "unconnected-(U3-PC14-OSC32-IN-Pad3)") (class "Default")
      (node (ref "U3") (pin "3") (pinfunction "PC14-OSC32-IN_3") (pintype "passive"))
    )
    (net (code "77") (name "unconnected-(U3-PC15-OSC32-OUT-Pad4)") (class "Default")
      (node (ref "U3") (pin "4") (pinfunction "PC15-OSC32-OUT_4") (pintype "passive"))
    )
    (net (code "78") (name "unconnected-(U3-PD2-Pad54)") (class "Default")
      (node (ref "U3") (pin "54") (pinfunction "PD2_54") (pintype "passive"))
    )
  )
)
